# MyRIO_Breakout_Gamma2d.net
KiCad netlist of a schematic drawn in EAGLE
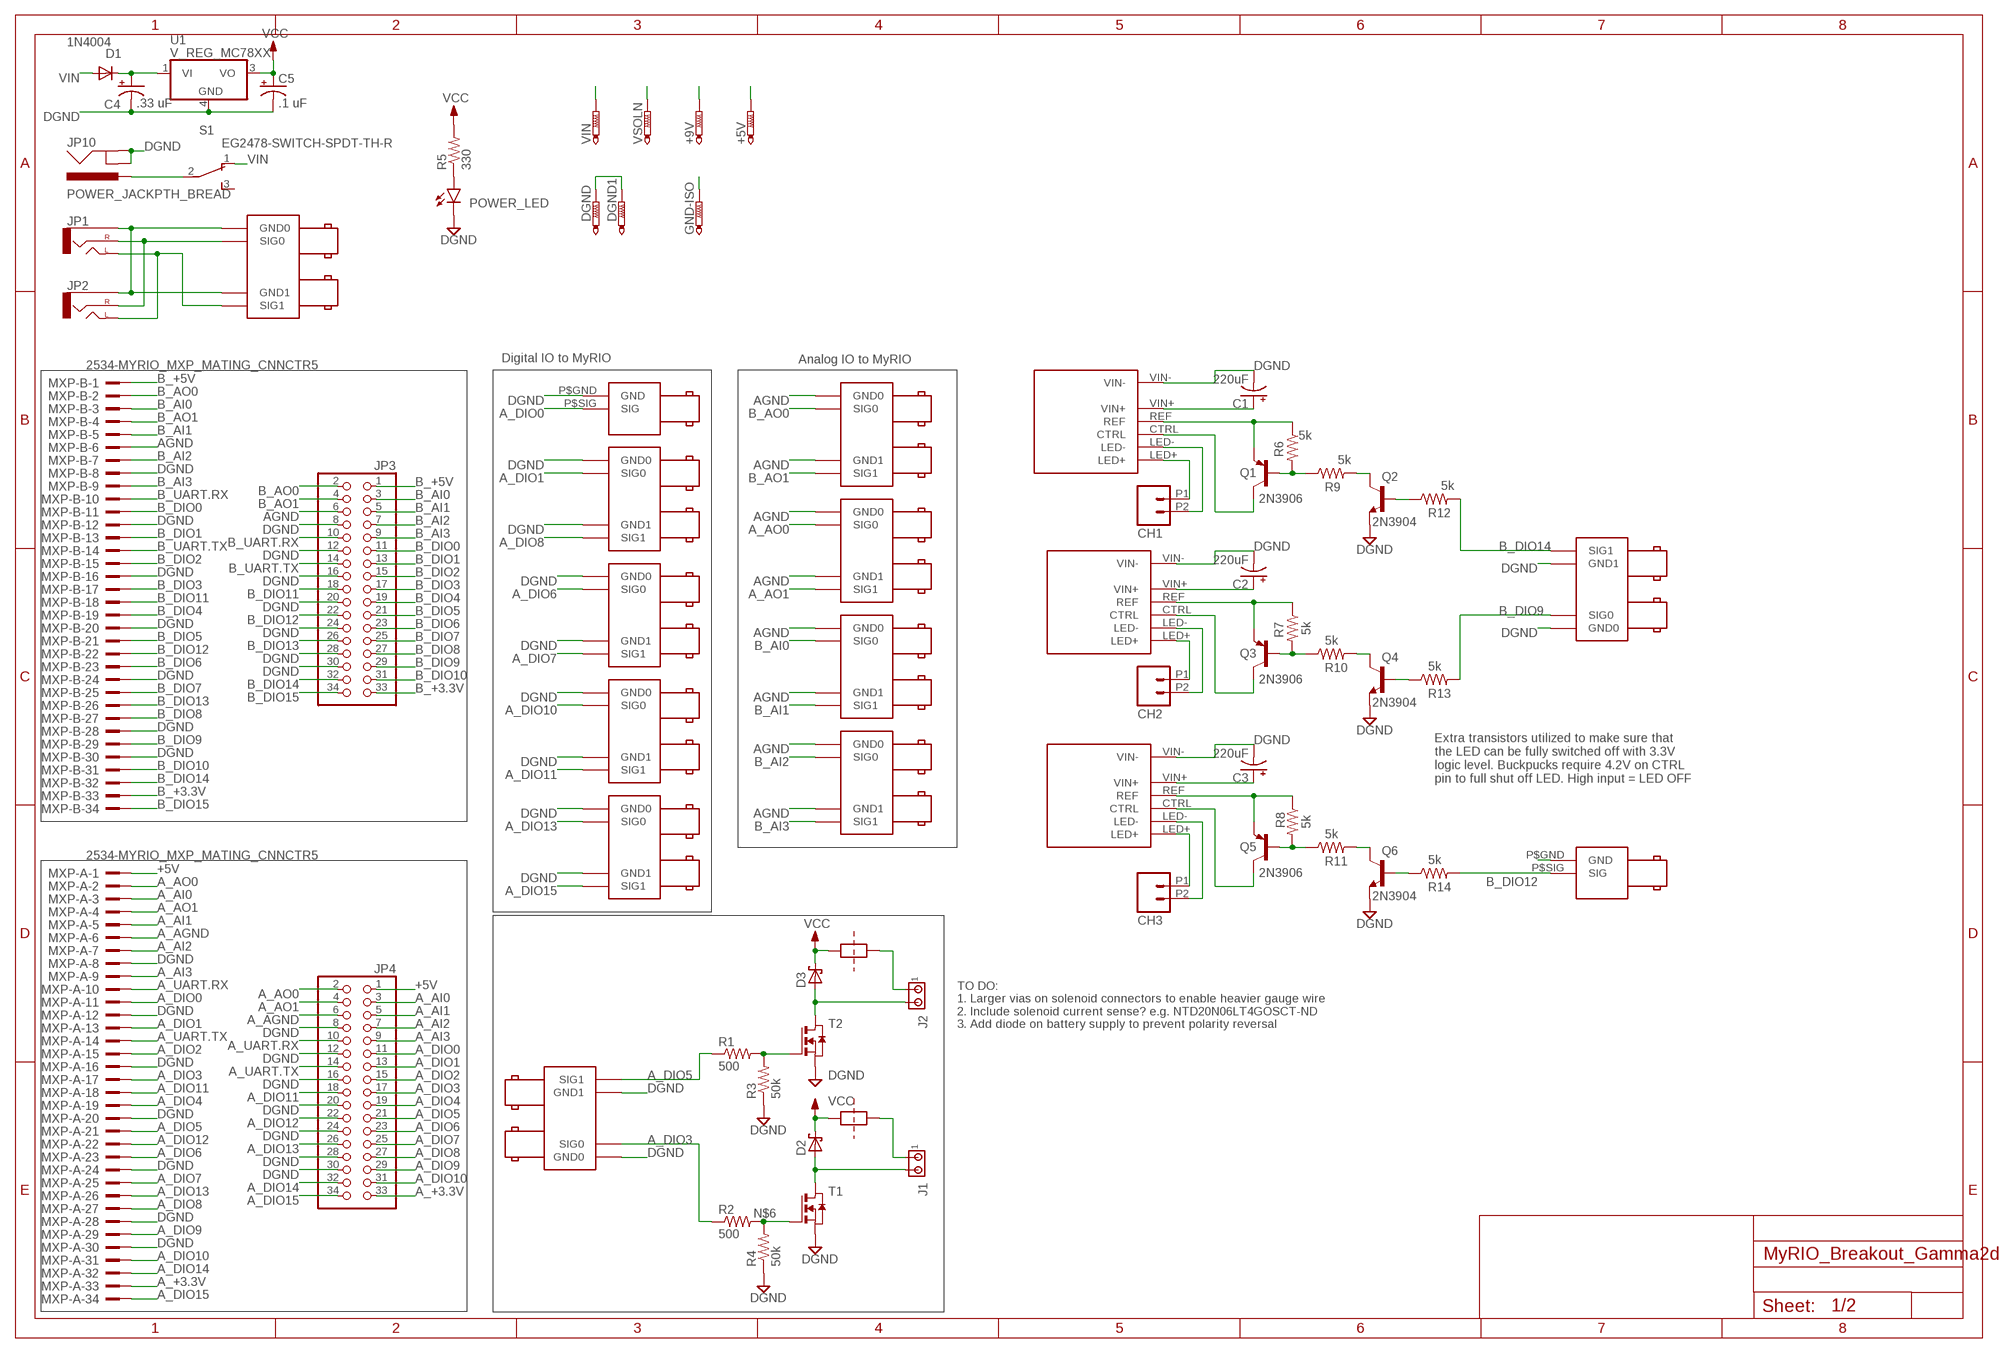
[diagram p0: schematic, sheet 1]
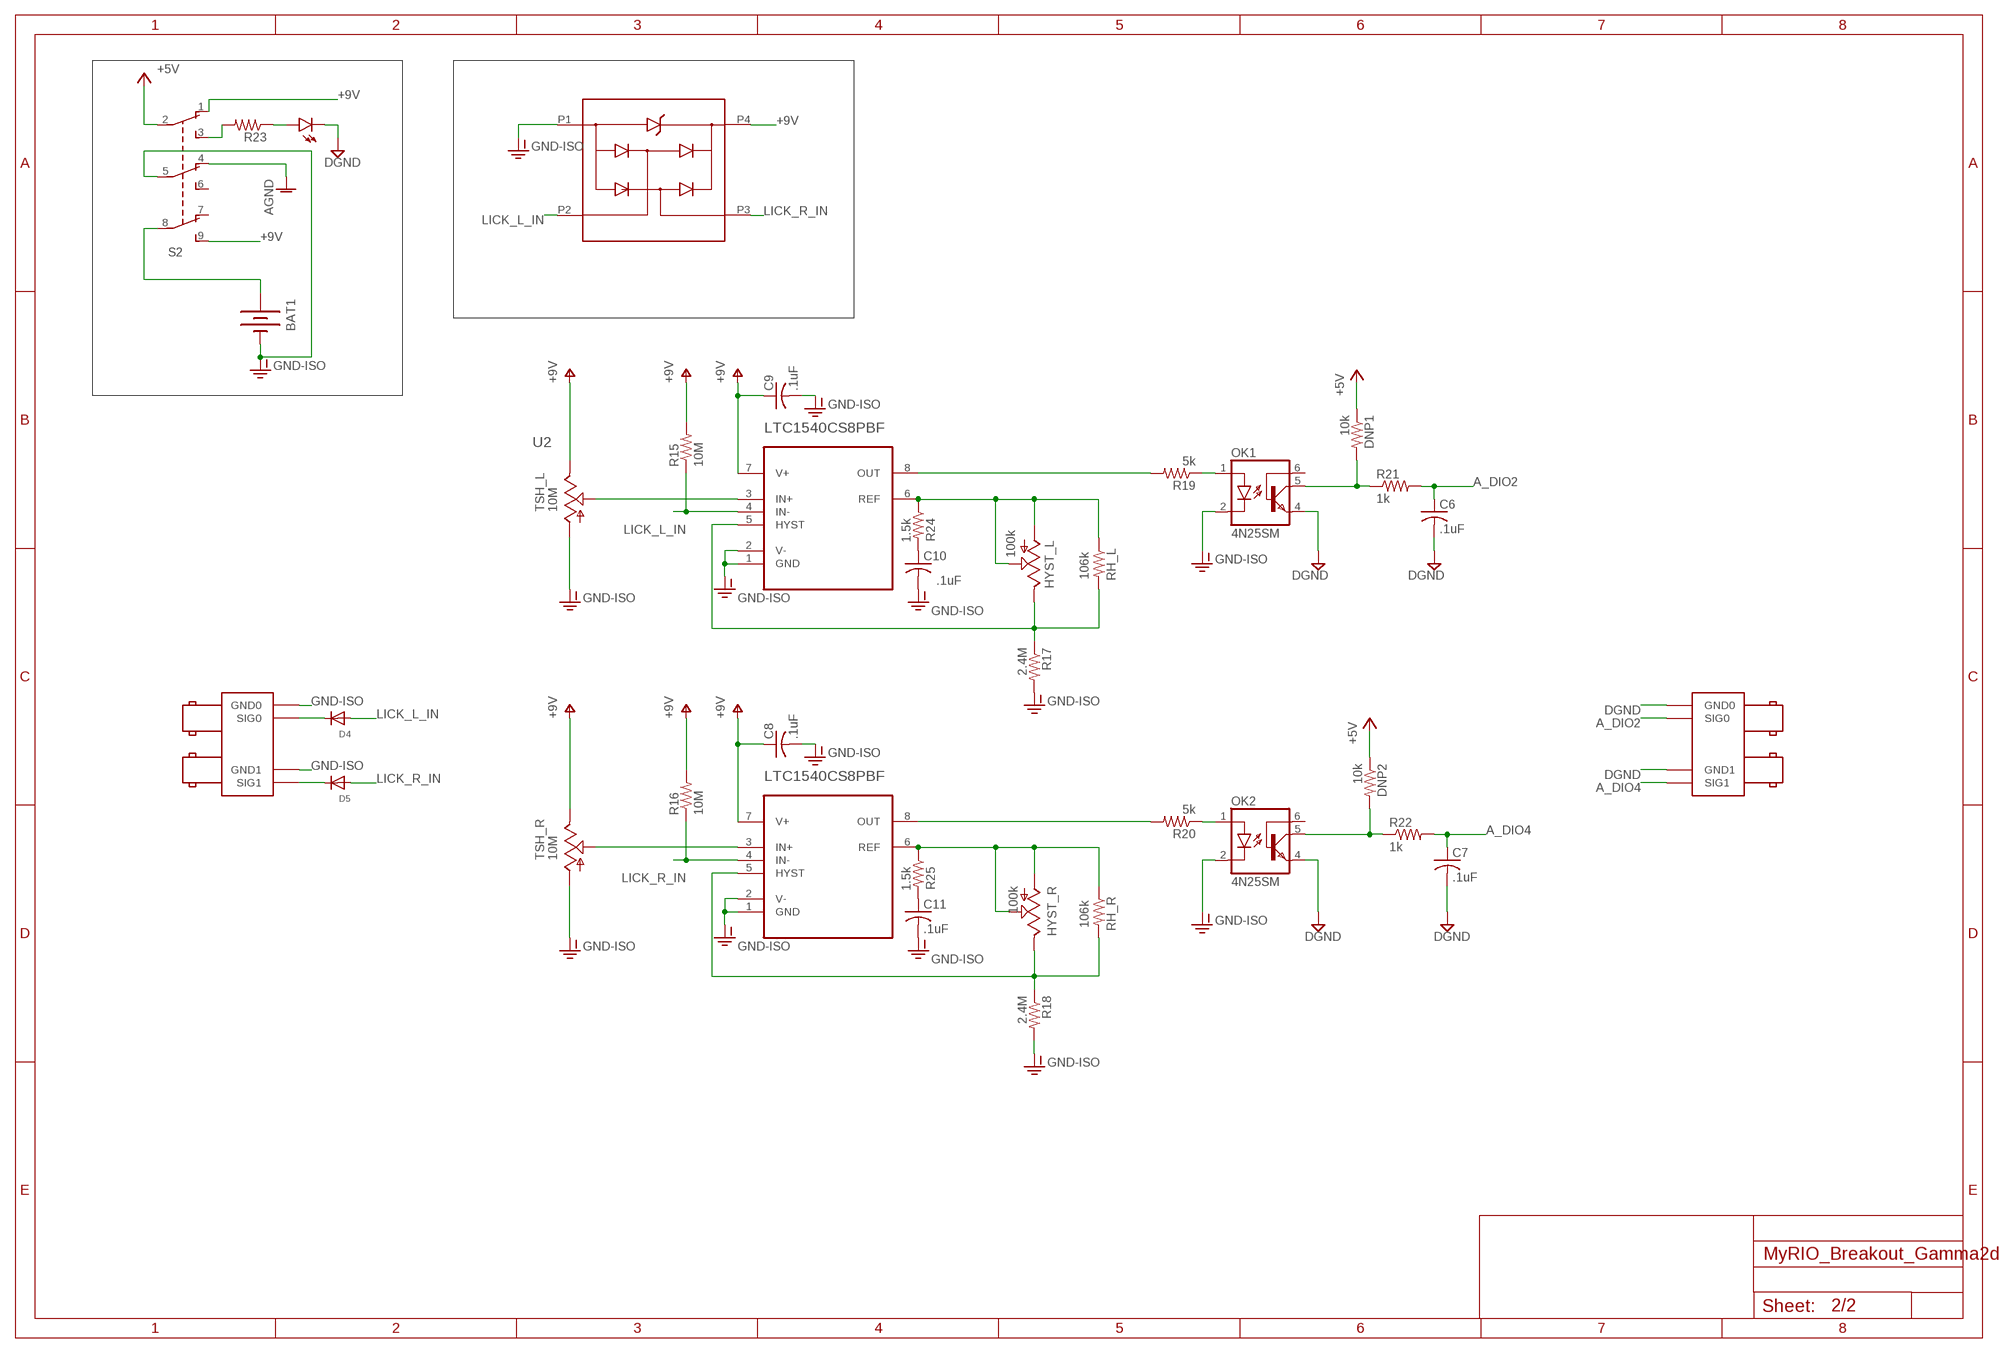
[diagram p1: schematic, sheet 2]

(export (version "E")
  (design (tool "Eeschema 10.0.6"))
  (components
    (comp (ref "+5V")
      (value "PTR1PAD1-13Y")
      (footprint "eagle-import:P1-13Y")
      (libsource (lib "eagle-import") (part "PTR1PAD1-13Y"))
    )
    (comp (ref "+9V")
      (value "PTR1PAD1-13Y")
      (footprint "eagle-import:P1-13Y")
      (libsource (lib "eagle-import") (part "PTR1PAD1-13Y"))
    )
    (comp (ref "AAO_0,1")
      (value "BNC_RIGHT_ANGLE_DOUBLE")
      (footprint "eagle-import:BNC_RIGHT_ANGLE_DOUBLE")
      (libsource (lib "eagle-import") (part "BNC_RIGHT_ANGLE_DOUBLE"))
    )
    (comp (ref "ACTV_REC")
      (value "BNC_RIGHT_ANGLE")
      (footprint "eagle-import:BNC_RIGHT_ANGLE")
      (libsource (lib "eagle-import") (part "BNC_RIGHT_ANGLE"))
    )
    (comp (ref "AUDIO")
      (value "BNC_RIGHT_ANGLE_DOUBLE")
      (footprint "eagle-import:BNC_RIGHT_ANGLE_DOUBLE")
      (libsource (lib "eagle-import") (part "BNC_RIGHT_ANGLE_DOUBLE"))
    )
    (comp (ref "BAI_0,1")
      (value "BNC_RIGHT_ANGLE_DOUBLE")
      (footprint "eagle-import:BNC_RIGHT_ANGLE_DOUBLE")
      (libsource (lib "eagle-import") (part "BNC_RIGHT_ANGLE_DOUBLE"))
    )
    (comp (ref "BAI_2,3")
      (value "BNC_RIGHT_ANGLE_DOUBLE")
      (footprint "eagle-import:BNC_RIGHT_ANGLE_DOUBLE")
      (libsource (lib "eagle-import") (part "BNC_RIGHT_ANGLE_DOUBLE"))
    )
    (comp (ref "BAO_0,1")
      (value "BNC_RIGHT_ANGLE_DOUBLE")
      (footprint "eagle-import:BNC_RIGHT_ANGLE_DOUBLE")
      (libsource (lib "eagle-import") (part "BNC_RIGHT_ANGLE_DOUBLE"))
    )
    (comp (ref "BUCKPUCK1")
      (value "BUCKPUCK-350-I")
      (footprint "eagle-import:BUCKPUCK_I")
      (libsource (lib "eagle-import") (part "BUCKPUCK--?I350"))
    )
    (comp (ref "BUCKPUCK2")
      (value "BUCKPUCK-350-I")
      (footprint "eagle-import:BUCKPUCK_I")
      (libsource (lib "eagle-import") (part "BUCKPUCK--?I350"))
    )
    (comp (ref "BUCKPUCK3")
      (value "BUCKPUCK-350-I")
      (footprint "eagle-import:BUCKPUCK_I")
      (libsource (lib "eagle-import") (part "BUCKPUCK--?I350"))
    )
    (comp (ref "C1")
      (value "220uF")
      (footprint "eagle-import:E5-10,5")
      (libsource (lib "eagle-import") (part "CPOL-USE5-10.5"))
    )
    (comp (ref "C2")
      (value "220uF")
      (footprint "eagle-import:E5-10,5")
      (libsource (lib "eagle-import") (part "CPOL-USE5-10.5"))
    )
    (comp (ref "C3")
      (value "220uF")
      (footprint "eagle-import:E5-10,5")
      (libsource (lib "eagle-import") (part "CPOL-USE5-10.5"))
    )
    (comp (ref "C4")
      (value ".33 uF")
      (footprint "eagle-import:E2,5-5")
      (libsource (lib "eagle-import") (part "CPOL-USE2.5-5"))
    )
    (comp (ref "C5")
      (value ".1 uF")
      (footprint "eagle-import:E2,5-5")
      (libsource (lib "eagle-import") (part "CPOL-USE2.5-5"))
    )
    (comp (ref "CAMERA")
      (value "BNC_RIGHT_ANGLE_DOUBLE")
      (footprint "eagle-import:BNC_RIGHT_ANGLE_DOUBLE")
      (libsource (lib "eagle-import") (part "BNC_RIGHT_ANGLE_DOUBLE"))
    )
    (comp (ref "CH1")
      (value "M022.54MM_SCREWTERM")
      (footprint "eagle-import:1X02_2.54_SCREWTERM")
      (libsource (lib "eagle-import") (part "M022.54MM_SCREWTERM"))
    )
    (comp (ref "CH2")
      (value "M022.54MM_SCREWTERM")
      (footprint "eagle-import:1X02_2.54_SCREWTERM")
      (libsource (lib "eagle-import") (part "M022.54MM_SCREWTERM"))
    )
    (comp (ref "CH3")
      (value "M022.54MM_SCREWTERM")
      (footprint "eagle-import:1X02_2.54_SCREWTERM")
      (libsource (lib "eagle-import") (part "M022.54MM_SCREWTERM"))
    )
    (comp (ref "D1")
      (value "1N4004")
      (footprint "eagle-import:DO41-10")
      (libsource (lib "eagle-import") (part "1N4004"))
    )
    (comp (ref "D2")
      (value "SCHOTTKY-DIODE")
      (footprint "eagle-import:DIODE_SMB")
      (libsource (lib "eagle-import") (part "SCHOTTKY-DIODE"))
    )
    (comp (ref "D3")
      (value "SCHOTTKY-DIODE")
      (footprint "eagle-import:DIODE_SMB")
      (libsource (lib "eagle-import") (part "SCHOTTKY-DIODE"))
    )
    (comp (ref "DGND")
      (value "PTR1PAD1-13Y")
      (footprint "eagle-import:P1-13Y")
      (libsource (lib "eagle-import") (part "PTR1PAD1-13Y"))
    )
    (comp (ref "DGND1")
      (value "PTR1PAD1-13Y")
      (footprint "eagle-import:P1-13Y")
      (libsource (lib "eagle-import") (part "PTR1PAD1-13Y"))
    )
    (comp (ref "D_FREE1_2")
      (value "BNC_RIGHT_ANGLE_DOUBLE")
      (footprint "eagle-import:BNC_RIGHT_ANGLE_DOUBLE")
      (libsource (lib "eagle-import") (part "BNC_RIGHT_ANGLE_DOUBLE"))
    )
    (comp (ref "D_FREE3_4")
      (value "BNC_RIGHT_ANGLE_DOUBLE")
      (footprint "eagle-import:BNC_RIGHT_ANGLE_DOUBLE")
      (libsource (lib "eagle-import") (part "BNC_RIGHT_ANGLE_DOUBLE"))
    )
    (comp (ref "GND-ISO")
      (value "PTR1PAD1-13Y")
      (footprint "eagle-import:P1-13Y")
      (libsource (lib "eagle-import") (part "PTR1PAD1-13Y"))
    )
    (comp (ref "J1")
      (value "MTA02-100")
      (footprint "eagle-import:10X02MTA")
      (libsource (lib "eagle-import") (part "MTA02-100"))
    )
    (comp (ref "J2")
      (value "MTA02-100")
      (footprint "eagle-import:10X02MTA")
      (libsource (lib "eagle-import") (part "MTA02-100"))
    )
    (comp (ref "JP1")
      (value "AUDIO-JACKPTH")
      (footprint "eagle-import:AUDIO-JACK")
      (libsource (lib "eagle-import") (part "AUDIO-JACKPTH"))
    )
    (comp (ref "JP2")
      (value "AUDIO-JACKPTH")
      (footprint "eagle-import:AUDIO-JACK")
      (libsource (lib "eagle-import") (part "AUDIO-JACKPTH"))
    )
    (comp (ref "JP3")
      (value "PINHD-2X17")
      (footprint "eagle-import:2X17")
      (libsource (lib "eagle-import") (part "PINHD-2X17"))
    )
    (comp (ref "JP4")
      (value "PINHD-2X17")
      (footprint "eagle-import:2X17")
      (libsource (lib "eagle-import") (part "PINHD-2X17"))
    )
    (comp (ref "JP5")
      (value "CUTABLE_RESISTOR_JUMPER1206")
      (footprint "eagle-import:1206_WITH_TRACE")
      (libsource (lib "eagle-import") (part "CUTABLE_RESISTOR_JUMPER1206"))
    )
    (comp (ref "JP6")
      (value "CUTABLE_RESISTOR_JUMPER1206")
      (footprint "eagle-import:1206_WITH_TRACE")
      (libsource (lib "eagle-import") (part "CUTABLE_RESISTOR_JUMPER1206"))
    )
    (comp (ref "JP10")
      (value "POWER_JACKPTH_BREAD")
      (footprint "eagle-import:POWER_JACK_PTH_BREAD")
      (libsource (lib "eagle-import") (part "POWER_JACKPTH_BREAD"))
    )
    (comp (ref "LED_CUE_3")
      (value "BNC_RIGHT_ANGLE")
      (footprint "eagle-import:BNC_RIGHT_ANGLE")
      (libsource (lib "eagle-import") (part "BNC_RIGHT_ANGLE"))
    )
    (comp (ref "LED_MASK_1,2")
      (value "BNC_RIGHT_ANGLE_DOUBLE")
      (footprint "eagle-import:BNC_RIGHT_ANGLE_DOUBLE")
      (libsource (lib "eagle-import") (part "BNC_RIGHT_ANGLE_DOUBLE"))
    )
    (comp (ref "MXP-A")
      (value "2534-MYRIO_MXP_MATING_CNNCTR5")
      (footprint "eagle-import:PAK100_2500-5-34-MXP_CONNCTR")
      (libsource (lib "eagle-import") (part "2534-MYRIO_MXP_MATING_CNNCTR5"))
    )
    (comp (ref "MXP-B")
      (value "2534-MYRIO_MXP_MATING_CNNCTR5")
      (footprint "eagle-import:PAK100_2500-5-34-MXP_CONNCTR")
      (libsource (lib "eagle-import") (part "2534-MYRIO_MXP_MATING_CNNCTR5"))
    )
    (comp (ref "POWER_LED")
      (value "LED3MM")
      (footprint "eagle-import:LED3MM")
      (libsource (lib "eagle-import") (part "LED3MM"))
    )
    (comp (ref "Q1")
      (value "2N3906")
      (footprint "eagle-import:SOT23-BEC")
      (libsource (lib "eagle-import") (part "-PNP-SOT23-BECMMBT3906LT1"))
    )
    (comp (ref "Q2")
      (value "2N3904")
      (footprint "eagle-import:SOT23-BEC")
      (libsource (lib "eagle-import") (part "-NPN-SOT23-BECMMBT3904LT1"))
    )
    (comp (ref "Q3")
      (value "2N3906")
      (footprint "eagle-import:SOT23-BEC")
      (libsource (lib "eagle-import") (part "-PNP-SOT23-BECMMBT3906LT1"))
    )
    (comp (ref "Q4")
      (value "2N3904")
      (footprint "eagle-import:SOT23-BEC")
      (libsource (lib "eagle-import") (part "-NPN-SOT23-BECMMBT3904LT1"))
    )
    (comp (ref "Q5")
      (value "2N3906")
      (footprint "eagle-import:SOT23-BEC")
      (libsource (lib "eagle-import") (part "-PNP-SOT23-BECMMBT3906LT1"))
    )
    (comp (ref "Q6")
      (value "2N3904")
      (footprint "eagle-import:SOT23-BEC")
      (libsource (lib "eagle-import") (part "-NPN-SOT23-BECMMBT3904LT1"))
    )
    (comp (ref "R1")
      (value "500")
      (footprint "eagle-import:M1206")
      (libsource (lib "eagle-import") (part "R-US_M1206"))
    )
    (comp (ref "R2")
      (value "500")
      (footprint "eagle-import:M1206")
      (libsource (lib "eagle-import") (part "R-US_M1206"))
    )
    (comp (ref "R3")
      (value "50k")
      (footprint "eagle-import:M1206")
      (libsource (lib "eagle-import") (part "R-US_M1206"))
    )
    (comp (ref "R4")
      (value "50k")
      (footprint "eagle-import:M1206")
      (libsource (lib "eagle-import") (part "R-US_M1206"))
    )
    (comp (ref "R5")
      (value "330")
      (footprint "eagle-import:0207_10")
      (libsource (lib "eagle-import") (part "R-US_0207/10"))
    )
    (comp (ref "R6")
      (value "5k")
      (footprint "eagle-import:0805S")
      (libsource (lib "eagle-import") (part "RESISTOR_SM0805S"))
    )
    (comp (ref "R7")
      (value "5k")
      (footprint "eagle-import:0805S")
      (libsource (lib "eagle-import") (part "RESISTOR_SM0805S"))
    )
    (comp (ref "R8")
      (value "5k")
      (footprint "eagle-import:0805S")
      (libsource (lib "eagle-import") (part "RESISTOR_SM0805S"))
    )
    (comp (ref "R9")
      (value "5k")
      (footprint "eagle-import:0805S")
      (libsource (lib "eagle-import") (part "RESISTOR_SM0805S"))
    )
    (comp (ref "R10")
      (value "5k")
      (footprint "eagle-import:0805S")
      (libsource (lib "eagle-import") (part "RESISTOR_SM0805S"))
    )
    (comp (ref "R11")
      (value "5k")
      (footprint "eagle-import:0805S")
      (libsource (lib "eagle-import") (part "RESISTOR_SM0805S"))
    )
    (comp (ref "R12")
      (value "5k")
      (footprint "eagle-import:0805S")
      (libsource (lib "eagle-import") (part "RESISTOR_SM0805S"))
    )
    (comp (ref "R13")
      (value "5k")
      (footprint "eagle-import:0805S")
      (libsource (lib "eagle-import") (part "RESISTOR_SM0805S"))
    )
    (comp (ref "R14")
      (value "5k")
      (footprint "eagle-import:0805S")
      (libsource (lib "eagle-import") (part "RESISTOR_SM0805S"))
    )
    (comp (ref "S1")
      (value "EG2478-SWITCH-SPDT-TH-R")
      (footprint "eagle-import:ESWITCH_500-SSP1M6")
      (libsource (lib "eagle-import") (part "EG2478-SWITCH-SPDT-TH-R"))
    )
    (comp (ref "SHUTTER")
      (value "BNC_RIGHT_ANGLE_DOUBLE")
      (footprint "eagle-import:BNC_RIGHT_ANGLE_DOUBLE")
      (libsource (lib "eagle-import") (part "BNC_RIGHT_ANGLE_DOUBLE"))
    )
    (comp (ref "SLN")
      (value "BNC_RIGHT_ANGLE_DOUBLE")
      (footprint "eagle-import:BNC_RIGHT_ANGLE_DOUBLE")
      (libsource (lib "eagle-import") (part "BNC_RIGHT_ANGLE_DOUBLE"))
    )
    (comp (ref "T1")
      (value "NMOSSOT223")
      (footprint "eagle-import:SOT223")
      (libsource (lib "eagle-import") (part "NMOSSOT223"))
    )
    (comp (ref "T2")
      (value "NMOSSOT223")
      (footprint "eagle-import:SOT223")
      (libsource (lib "eagle-import") (part "NMOSSOT223"))
    )
    (comp (ref "U1")
      (value "V_REG_MC78XX")
      (footprint "eagle-import:DPAK")
      (libsource (lib "eagle-import") (part "V_REG_MC78XX"))
    )
    (comp (ref "VIN")
      (value "PTR1PAD1-13Y")
      (footprint "eagle-import:P1-13Y")
      (libsource (lib "eagle-import") (part "PTR1PAD1-13Y"))
    )
    (comp (ref "VSOLN")
      (value "PTR1PAD1-13Y")
      (footprint "eagle-import:P1-13Y")
      (libsource (lib "eagle-import") (part "PTR1PAD1-13Y"))
    )
    (comp (ref "BAT1")
      (value "BATTERY9V")
      (footprint "eagle-import:BATTCON_9V")
      (libsource (lib "eagle-import") (part "BATTERY9V"))
    )
    (comp (ref "C6")
      (value ".1uF")
      (footprint "eagle-import:C0805")
      (libsource (lib "eagle-import") (part "C-USC0805"))
    )
    (comp (ref "C7")
      (value ".1uF")
      (footprint "eagle-import:C0805")
      (fields (field (name "SPICEPREFIX") "C"))
      (libsource (lib "eagle-import") (part "C-USC0805"))
    )
    (comp (ref "C8")
      (value ".1uF")
      (footprint "eagle-import:C0805")
      (fields (field (name "SPICEPREFIX") "C"))
      (libsource (lib "eagle-import") (part "C-USC0805"))
    )
    (comp (ref "C9")
      (value ".1uF")
      (footprint "eagle-import:C0805")
      (fields (field (name "SPICEPREFIX") "C"))
      (libsource (lib "eagle-import") (part "C-USC0805"))
    )
    (comp (ref "C10")
      (value ".1uF")
      (footprint "eagle-import:C0805")
      (fields (field (name "SPICEPREFIX") "C"))
      (libsource (lib "eagle-import") (part "C-USC0805"))
    )
    (comp (ref "C11")
      (value ".1uF")
      (footprint "eagle-import:C0805")
      (fields (field (name "SPICEPREFIX") "C"))
      (libsource (lib "eagle-import") (part "C-USC0805"))
    )
    (comp (ref "D4")
      (value "DIODE_SOD-123FL")
      (footprint "eagle-import:SOD-123FL")
      (libsource (lib "eagle-import") (part "DIODE_SOD-123FL"))
    )
    (comp (ref "D5")
      (value "DIODE_SOD-123FL")
      (footprint "eagle-import:SOD-123FL")
      (libsource (lib "eagle-import") (part "DIODE_SOD-123FL"))
    )
    (comp (ref "DNP1")
      (value "10k")
      (footprint "eagle-import:M0805")
      (libsource (lib "eagle-import") (part "R-US_M0805"))
    )
    (comp (ref "DNP2")
      (value "10k")
      (footprint "eagle-import:M0805")
      (fields (field (name "SPICEPREFIX") "R"))
      (libsource (lib "eagle-import") (part "R-US_M0805"))
    )
    (comp (ref "HYST_L")
      (value "100k")
      (footprint "eagle-import:B25P")
      (libsource (lib "eagle-import") (part "TRIM_US-B25P"))
    )
    (comp (ref "HYST_R")
      (value "100k")
      (footprint "eagle-import:B25P")
      (fields (field (name "SPICEPREFIX") "J"))
      (libsource (lib "eagle-import") (part "TRIM_US-B25P"))
    )
    (comp (ref "ISOLATED")
      (value "LED3MM")
      (footprint "eagle-import:LED3MM")
      (libsource (lib "eagle-import") (part "LED3MM"))
    )
    (comp (ref "LICK")
      (value "BNC_RIGHT_ANGLE_DOUBLE")
      (footprint "eagle-import:BNC_RIGHT_ANGLE_DOUBLE")
      (libsource (lib "eagle-import") (part "BNC_RIGHT_ANGLE_DOUBLE"))
    )
    (comp (ref "LICK_INPUTS")
      (value "BNC_RIGHT_ANGLE_DOUBLE")
      (footprint "eagle-import:BNC_RIGHT_ANGLE_DOUBLE")
      (libsource (lib "eagle-import") (part "BNC_RIGHT_ANGLE_DOUBLE"))
    )
    (comp (ref "OK1")
      (value "4N25SM")
      (footprint "eagle-import:DIL6-SMD")
      (fields (field (name "MF") "FAIRCHILD SEMICONDUCTOR"))
      (libsource (lib "eagle-import") (part "4N?MS25"))
    )
    (comp (ref "OK2")
      (value "4N25SM")
      (footprint "eagle-import:DIL6-SMD")
      (fields (field (name "MF") "FAIRCHILD SEMICONDUCTOR") (field (name "SPICEPREFIX") "X"))
      (libsource (lib "eagle-import") (part "4N?MS25"))
    )
    (comp (ref "R15")
      (value "10M")
      (footprint "eagle-import:M0805")
      (fields (field (name "SPICEPREFIX") "R"))
      (libsource (lib "eagle-import") (part "R-US_M0805"))
    )
    (comp (ref "R16")
      (value "10M")
      (footprint "eagle-import:M0805")
      (fields (field (name "SPICEPREFIX") "R"))
      (libsource (lib "eagle-import") (part "R-US_M0805"))
    )
    (comp (ref "R17")
      (value "2.4M")
      (footprint "eagle-import:M0805")
      (libsource (lib "eagle-import") (part "R-US_M0805"))
    )
    (comp (ref "R18")
      (value "2.4M")
      (footprint "eagle-import:M0805")
      (fields (field (name "SPICEPREFIX") "R"))
      (libsource (lib "eagle-import") (part "R-US_M0805"))
    )
    (comp (ref "R19")
      (value "5k")
      (footprint "eagle-import:M0805")
      (libsource (lib "eagle-import") (part "R-US_M0805"))
    )
    (comp (ref "R20")
      (value "5k")
      (footprint "eagle-import:M0805")
      (fields (field (name "SPICEPREFIX") "R"))
      (libsource (lib "eagle-import") (part "R-US_M0805"))
    )
    (comp (ref "R21")
      (value "1k")
      (footprint "eagle-import:M0805")
      (libsource (lib "eagle-import") (part "R-US_M0805"))
    )
    (comp (ref "R22")
      (value "1k")
      (footprint "eagle-import:M0805")
      (fields (field (name "SPICEPREFIX") "R"))
      (libsource (lib "eagle-import") (part "R-US_M0805"))
    )
    (comp (ref "R23")
      (value "330")
      (footprint "eagle-import:0207_10")
      (libsource (lib "eagle-import") (part "R-US_0207/10"))
    )
    (comp (ref "R24")
      (value "1.5k")
      (footprint "eagle-import:M0805")
      (libsource (lib "eagle-import") (part "R-US_M0805"))
    )
    (comp (ref "R25")
      (value "1.5k")
      (footprint "eagle-import:M0805")
      (libsource (lib "eagle-import") (part "R-US_M0805"))
    )
    (comp (ref "RH_L")
      (value "106k")
      (footprint "eagle-import:M0805")
      (libsource (lib "eagle-import") (part "R-US_M0805"))
    )
    (comp (ref "RH_R")
      (value "106k")
      (footprint "eagle-import:M0805")
      (libsource (lib "eagle-import") (part "R-US_M0805"))
    )
    (comp (ref "S2")
      (value "SWITCH-3PDT-TH-V")
      (footprint "eagle-import:NKK-M20-9PIN-VERTICAL")
      (libsource (lib "eagle-import") (part "SWITCH-3PDT-TH-V"))
    )
    (comp (ref "TSH_L")
      (value "10M")
      (footprint "eagle-import:B25P")
      (libsource (lib "eagle-import") (part "TRIM_US-B25P"))
    )
    (comp (ref "TSH_R")
      (value "10M")
      (footprint "eagle-import:B25P")
      (libsource (lib "eagle-import") (part "TRIM_US-B25P"))
    )
    (comp (ref "U$1")
      (value "CD143A-12_TVS")
      (footprint "eagle-import:SOT-143")
      (libsource (lib "eagle-import") (part "CD143A-12_TVS"))
    )
    (comp (ref "U2")
      (value "LTC1540CS8PBF")
      (footprint "eagle-import:SOIC127P600X175-8N")
      (fields (field (name "MF") "Linear Technology/Analog") (field (name "MP") "LTC1540CS8#PBF"))
      (libsource (lib "eagle-import") (part "LTC1540CS8PBF"))
    )
    (comp (ref "U3")
      (value "LTC1540CS8PBF")
      (footprint "eagle-import:SOIC127P600X175-8N")
      (fields
        (field (name "MF") "Linear Technology/Analog")
        (field (name "MP") "LTC1540CS8#PBF")
        (field (name "SPICEPREFIX") "X")
      )
      (libsource (lib "eagle-import") (part "LTC1540CS8PBF"))
    )
  )
  (nets
    (net (code "1") (name "+5V") (class "Default")
      (node (ref "+5V") (pin "TP") (pinfunction "TP_TP") (pintype "input"))
      (node (ref "DNP1") (pin "1") (pinfunction "1_1") (pintype "passive"))
      (node (ref "DNP2") (pin "1") (pinfunction "1_1") (pintype "passive"))
      (node (ref "JP4") (pin "1") (pinfunction "1_1") (pintype "passive"))
      (node (ref "MXP-A") (pin "1") (pinfunction "KL_1") (pintype "passive"))
      (node (ref "S2") (pin "2") (pinfunction "P1_2") (pintype "passive"))
    )
    (net (code "2") (name "+9V") (class "Default")
      (node (ref "+9V") (pin "TP") (pinfunction "TP_TP") (pintype "input"))
      (node (ref "C8") (pin "1") (pinfunction "1_1") (pintype "passive"))
      (node (ref "C9") (pin "1") (pinfunction "1_1") (pintype "passive"))
      (node (ref "R15") (pin "2") (pinfunction "2_2") (pintype "passive"))
      (node (ref "R16") (pin "2") (pinfunction "2_2") (pintype "passive"))
      (node (ref "S2") (pin "1") (pinfunction "O1_1") (pintype "passive"))
      (node (ref "S2") (pin "9") (pinfunction "S3_9") (pintype "passive"))
      (node (ref "TSH_L") (pin "E") (pinfunction "E_E") (pintype "passive"))
      (node (ref "TSH_R") (pin "E") (pinfunction "E_E") (pintype "passive"))
      (node (ref "U$1") (pin "P4") (pinfunction "P$4_P4") (pintype "bidirectional"))
      (node (ref "U2") (pin "7") (pinfunction "V+_7") (pintype "power_in"))
      (node (ref "U3") (pin "7") (pinfunction "V+_7") (pintype "power_in"))
    )
    (net (code "3") (name "AGND") (class "Default")
      (node (ref "AAO_0,1") (pin "P$GND0") (pinfunction "GND0_P$GND0") (pintype "bidirectional"))
      (node (ref "AAO_0,1") (pin "P$GND1") (pinfunction "GND1_P$GND1") (pintype "bidirectional"))
      (node (ref "BAI_0,1") (pin "P$GND0") (pinfunction "GND0_P$GND0") (pintype "bidirectional"))
      (node (ref "BAI_0,1") (pin "P$GND1") (pinfunction "GND1_P$GND1") (pintype "bidirectional"))
      (node (ref "BAI_2,3") (pin "P$GND0") (pinfunction "GND0_P$GND0") (pintype "bidirectional"))
      (node (ref "BAI_2,3") (pin "P$GND1") (pinfunction "GND1_P$GND1") (pintype "bidirectional"))
      (node (ref "BAO_0,1") (pin "P$GND0") (pinfunction "GND0_P$GND0") (pintype "bidirectional"))
      (node (ref "BAO_0,1") (pin "P$GND1") (pinfunction "GND1_P$GND1") (pintype "bidirectional"))
      (node (ref "JP3") (pin "6") (pinfunction "6_6") (pintype "passive"))
      (node (ref "MXP-B") (pin "6") (pinfunction "KL_6") (pintype "passive"))
      (node (ref "S2") (pin "4") (pinfunction "O2_4") (pintype "passive"))
    )
    (net (code "4") (name "A_+3.3V") (class "Default")
      (node (ref "JP4") (pin "33") (pinfunction "33_33") (pintype "passive"))
      (node (ref "MXP-A") (pin "33") (pinfunction "KL_33") (pintype "passive"))
    )
    (net (code "5") (name "A_AGND") (class "Default")
      (node (ref "JP4") (pin "6") (pinfunction "6_6") (pintype "passive"))
      (node (ref "MXP-A") (pin "6") (pinfunction "KL_6") (pintype "passive"))
    )
    (net (code "6") (name "A_AI0") (class "Default")
      (node (ref "JP4") (pin "3") (pinfunction "3_3") (pintype "passive"))
      (node (ref "MXP-A") (pin "3") (pinfunction "KL_3") (pintype "passive"))
    )
    (net (code "7") (name "A_AI1") (class "Default")
      (node (ref "JP4") (pin "5") (pinfunction "5_5") (pintype "passive"))
      (node (ref "MXP-A") (pin "5") (pinfunction "KL_5") (pintype "passive"))
    )
    (net (code "8") (name "A_AI2") (class "Default")
      (node (ref "JP4") (pin "7") (pinfunction "7_7") (pintype "passive"))
      (node (ref "MXP-A") (pin "7") (pinfunction "KL_7") (pintype "passive"))
    )
    (net (code "9") (name "A_AI3") (class "Default")
      (node (ref "JP4") (pin "9") (pinfunction "9_9") (pintype "passive"))
      (node (ref "MXP-A") (pin "9") (pinfunction "KL_9") (pintype "passive"))
    )
    (net (code "10") (name "A_AO0") (class "Default")
      (node (ref "AAO_0,1") (pin "P$SIG0") (pinfunction "SIG0_P$SIG0") (pintype "bidirectional"))
      (node (ref "JP4") (pin "2") (pinfunction "2_2") (pintype "passive"))
      (node (ref "MXP-A") (pin "2") (pinfunction "KL_2") (pintype "passive"))
    )
    (net (code "11") (name "A_AO1") (class "Default")
      (node (ref "AAO_0,1") (pin "P$SIG1") (pinfunction "SIG1_P$SIG1") (pintype "bidirectional"))
      (node (ref "JP4") (pin "4") (pinfunction "4_4") (pintype "passive"))
      (node (ref "MXP-A") (pin "4") (pinfunction "KL_4") (pintype "passive"))
    )
    (net (code "12") (name "A_DIO0") (class "Default")
      (node (ref "ACTV_REC") (pin "P$SIG") (pinfunction "SIG_P$SIG") (pintype "bidirectional"))
      (node (ref "JP4") (pin "11") (pinfunction "11_11") (pintype "passive"))
      (node (ref "MXP-A") (pin "11") (pinfunction "KL_11") (pintype "passive"))
    )
    (net (code "13") (name "A_DIO1") (class "Default")
      (node (ref "CAMERA") (pin "P$SIG0") (pinfunction "SIG0_P$SIG0") (pintype "bidirectional"))
      (node (ref "JP4") (pin "13") (pinfunction "13_13") (pintype "passive"))
      (node (ref "MXP-A") (pin "13") (pinfunction "KL_13") (pintype "passive"))
    )
    (net (code "14") (name "A_DIO2") (class "Default")
      (node (ref "C6") (pin "1") (pinfunction "1_1") (pintype "passive"))
      (node (ref "JP4") (pin "15") (pinfunction "15_15") (pintype "passive"))
      (node (ref "LICK") (pin "P$SIG0") (pinfunction "SIG0_P$SIG0") (pintype "bidirectional"))
      (node (ref "MXP-A") (pin "15") (pinfunction "KL_15") (pintype "passive"))
      (node (ref "R21") (pin "2") (pinfunction "2_2") (pintype "passive"))
    )
    (net (code "15") (name "A_DIO3") (class "Default")
      (node (ref "JP4") (pin "17") (pinfunction "17_17") (pintype "passive"))
      (node (ref "MXP-A") (pin "17") (pinfunction "KL_17") (pintype "passive"))
      (node (ref "R2") (pin "1") (pinfunction "1_1") (pintype "passive"))
      (node (ref "SLN") (pin "P$SIG0") (pinfunction "SIG0_P$SIG0") (pintype "bidirectional"))
    )
    (net (code "16") (name "A_DIO4") (class "Default")
      (node (ref "C7") (pin "1") (pinfunction "1_1") (pintype "passive"))
      (node (ref "JP4") (pin "19") (pinfunction "19_19") (pintype "passive"))
      (node (ref "LICK") (pin "P$SIG1") (pinfunction "SIG1_P$SIG1") (pintype "bidirectional"))
      (node (ref "MXP-A") (pin "19") (pinfunction "KL_19") (pintype "passive"))
      (node (ref "R22") (pin "2") (pinfunction "2_2") (pintype "passive"))
    )
    (net (code "17") (name "A_DIO5") (class "Default")
      (node (ref "JP4") (pin "21") (pinfunction "21_21") (pintype "passive"))
      (node (ref "MXP-A") (pin "21") (pinfunction "KL_21") (pintype "passive"))
      (node (ref "R1") (pin "1") (pinfunction "1_1") (pintype "passive"))
      (node (ref "SLN") (pin "P$SIG1") (pinfunction "SIG1_P$SIG1") (pintype "bidirectional"))
    )
    (net (code "18") (name "A_DIO6") (class "Default")
      (node (ref "JP4") (pin "23") (pinfunction "23_23") (pintype "passive"))
      (node (ref "MXP-A") (pin "23") (pinfunction "KL_23") (pintype "passive"))
      (node (ref "SHUTTER") (pin "P$SIG0") (pinfunction "SIG0_P$SIG0") (pintype "bidirectional"))
    )
    (net (code "19") (name "A_DIO7") (class "Default")
      (node (ref "JP4") (pin "25") (pinfunction "25_25") (pintype "passive"))
      (node (ref "MXP-A") (pin "25") (pinfunction "KL_25") (pintype "passive"))
      (node (ref "SHUTTER") (pin "P$SIG1") (pinfunction "SIG1_P$SIG1") (pintype "bidirectional"))
    )
    (net (code "20") (name "A_DIO8") (class "Default")
      (node (ref "CAMERA") (pin "P$SIG1") (pinfunction "SIG1_P$SIG1") (pintype "bidirectional"))
      (node (ref "JP4") (pin "27") (pinfunction "27_27") (pintype "passive"))
      (node (ref "MXP-A") (pin "27") (pinfunction "KL_27") (pintype "passive"))
    )
    (net (code "21") (name "A_DIO9") (class "Default")
      (node (ref "JP4") (pin "29") (pinfunction "29_29") (pintype "passive"))
      (node (ref "MXP-A") (pin "29") (pinfunction "KL_29") (pintype "passive"))
    )
    (net (code "22") (name "A_DIO10") (class "Default")
      (node (ref "D_FREE1_2") (pin "P$SIG0") (pinfunction "SIG0_P$SIG0") (pintype "bidirectional"))
      (node (ref "JP4") (pin "31") (pinfunction "31_31") (pintype "passive"))
      (node (ref "MXP-A") (pin "31") (pinfunction "KL_31") (pintype "passive"))
    )
    (net (code "23") (name "A_DIO11") (class "Default")
      (node (ref "D_FREE1_2") (pin "P$SIG1") (pinfunction "SIG1_P$SIG1") (pintype "bidirectional"))
      (node (ref "JP4") (pin "18") (pinfunction "18_18") (pintype "passive"))
      (node (ref "MXP-A") (pin "18") (pinfunction "KL_18") (pintype "passive"))
    )
    (net (code "24") (name "A_DIO12") (class "Default")
      (node (ref "JP4") (pin "22") (pinfunction "22_22") (pintype "passive"))
      (node (ref "MXP-A") (pin "22") (pinfunction "KL_22") (pintype "passive"))
    )
    (net (code "25") (name "A_DIO13") (class "Default")
      (node (ref "D_FREE3_4") (pin "P$SIG0") (pinfunction "SIG0_P$SIG0") (pintype "bidirectional"))
      (node (ref "JP4") (pin "26") (pinfunction "26_26") (pintype "passive"))
      (node (ref "MXP-A") (pin "26") (pinfunction "KL_26") (pintype "passive"))
    )
    (net (code "26") (name "A_DIO14") (class "Default")
      (node (ref "JP4") (pin "32") (pinfunction "32_32") (pintype "passive"))
      (node (ref "MXP-A") (pin "32") (pinfunction "KL_32") (pintype "passive"))
    )
    (net (code "27") (name "A_DIO15") (class "Default")
      (node (ref "D_FREE3_4") (pin "P$SIG1") (pinfunction "SIG1_P$SIG1") (pintype "bidirectional"))
      (node (ref "JP4") (pin "34") (pinfunction "34_34") (pintype "passive"))
      (node (ref "MXP-A") (pin "34") (pinfunction "KL_34") (pintype "passive"))
    )
    (net (code "28") (name "A_UART.RX") (class "Default")
      (node (ref "JP4") (pin "10") (pinfunction "10_10") (pintype "passive"))
      (node (ref "MXP-A") (pin "10") (pinfunction "KL_10") (pintype "passive"))
    )
    (net (code "29") (name "A_UART.TX") (class "Default")
      (node (ref "JP4") (pin "14") (pinfunction "14_14") (pintype "passive"))
      (node (ref "MXP-A") (pin "14") (pinfunction "KL_14") (pintype "passive"))
    )
    (net (code "30") (name "B_+3.3V") (class "Default")
      (node (ref "JP3") (pin "33") (pinfunction "33_33") (pintype "passive"))
      (node (ref "MXP-B") (pin "33") (pinfunction "KL_33") (pintype "passive"))
    )
    (net (code "31") (name "B_+5V") (class "Default")
      (node (ref "JP3") (pin "1") (pinfunction "1_1") (pintype "passive"))
      (node (ref "MXP-B") (pin "1") (pinfunction "KL_1") (pintype "passive"))
    )
    (net (code "32") (name "B_AI0") (class "Default")
      (node (ref "BAI_0,1") (pin "P$SIG0") (pinfunction "SIG0_P$SIG0") (pintype "bidirectional"))
      (node (ref "JP3") (pin "3") (pinfunction "3_3") (pintype "passive"))
      (node (ref "MXP-B") (pin "3") (pinfunction "KL_3") (pintype "passive"))
    )
    (net (code "33") (name "B_AI1") (class "Default")
      (node (ref "BAI_0,1") (pin "P$SIG1") (pinfunction "SIG1_P$SIG1") (pintype "bidirectional"))
      (node (ref "JP3") (pin "5") (pinfunction "5_5") (pintype "passive"))
      (node (ref "MXP-B") (pin "5") (pinfunction "KL_5") (pintype "passive"))
    )
    (net (code "34") (name "B_AI2") (class "Default")
      (node (ref "BAI_2,3") (pin "P$SIG0") (pinfunction "SIG0_P$SIG0") (pintype "bidirectional"))
      (node (ref "JP3") (pin "7") (pinfunction "7_7") (pintype "passive"))
      (node (ref "MXP-B") (pin "7") (pinfunction "KL_7") (pintype "passive"))
    )
    (net (code "35") (name "B_AI3") (class "Default")
      (node (ref "BAI_2,3") (pin "P$SIG1") (pinfunction "SIG1_P$SIG1") (pintype "bidirectional"))
      (node (ref "JP3") (pin "9") (pinfunction "9_9") (pintype "passive"))
      (node (ref "MXP-B") (pin "9") (pinfunction "KL_9") (pintype "passive"))
    )
    (net (code "36") (name "B_AO0") (class "Default")
      (node (ref "BAO_0,1") (pin "P$SIG0") (pinfunction "SIG0_P$SIG0") (pintype "bidirectional"))
      (node (ref "JP3") (pin "2") (pinfunction "2_2") (pintype "passive"))
      (node (ref "MXP-B") (pin "2") (pinfunction "KL_2") (pintype "passive"))
    )
    (net (code "37") (name "B_AO1") (class "Default")
      (node (ref "BAO_0,1") (pin "P$SIG1") (pinfunction "SIG1_P$SIG1") (pintype "bidirectional"))
      (node (ref "JP3") (pin "4") (pinfunction "4_4") (pintype "passive"))
      (node (ref "MXP-B") (pin "4") (pinfunction "KL_4") (pintype "passive"))
    )
    (net (code "38") (name "B_DIO0") (class "Default")
      (node (ref "JP3") (pin "11") (pinfunction "11_11") (pintype "passive"))
      (node (ref "MXP-B") (pin "11") (pinfunction "KL_11") (pintype "passive"))
    )
    (net (code "39") (name "B_DIO1") (class "Default")
      (node (ref "JP3") (pin "13") (pinfunction "13_13") (pintype "passive"))
      (node (ref "MXP-B") (pin "13") (pinfunction "KL_13") (pintype "passive"))
    )
    (net (code "40") (name "B_DIO2") (class "Default")
      (node (ref "JP3") (pin "15") (pinfunction "15_15") (pintype "passive"))
      (node (ref "MXP-B") (pin "15") (pinfunction "KL_15") (pintype "passive"))
    )
    (net (code "41") (name "B_DIO3") (class "Default")
      (node (ref "JP3") (pin "17") (pinfunction "17_17") (pintype "passive"))
      (node (ref "MXP-B") (pin "17") (pinfunction "KL_17") (pintype "passive"))
    )
    (net (code "42") (name "B_DIO4") (class "Default")
      (node (ref "JP3") (pin "19") (pinfunction "19_19") (pintype "passive"))
      (node (ref "MXP-B") (pin "19") (pinfunction "KL_19") (pintype "passive"))
    )
    (net (code "43") (name "B_DIO5") (class "Default")
      (node (ref "JP3") (pin "21") (pinfunction "21_21") (pintype "passive"))
      (node (ref "MXP-B") (pin "21") (pinfunction "KL_21") (pintype "passive"))
    )
    (net (code "44") (name "B_DIO6") (class "Default")
      (node (ref "JP3") (pin "23") (pinfunction "23_23") (pintype "passive"))
      (node (ref "MXP-B") (pin "23") (pinfunction "KL_23") (pintype "passive"))
    )
    (net (code "45") (name "B_DIO7") (class "Default")
      (node (ref "JP3") (pin "25") (pinfunction "25_25") (pintype "passive"))
      (node (ref "MXP-B") (pin "25") (pinfunction "KL_25") (pintype "passive"))
    )
    (net (code "46") (name "B_DIO8") (class "Default")
      (node (ref "JP3") (pin "27") (pinfunction "27_27") (pintype "passive"))
      (node (ref "MXP-B") (pin "27") (pinfunction "KL_27") (pintype "passive"))
    )
    (net (code "47") (name "B_DIO9") (class "Default")
      (node (ref "JP3") (pin "29") (pinfunction "29_29") (pintype "passive"))
      (node (ref "LED_MASK_1,2") (pin "P$SIG0") (pinfunction "SIG0_P$SIG0") (pintype "bidirectional"))
      (node (ref "MXP-B") (pin "29") (pinfunction "KL_29") (pintype "passive"))
      (node (ref "R13") (pin "2") (pinfunction "2_2") (pintype "passive"))
    )
    (net (code "48") (name "B_DIO10") (class "Default")
      (node (ref "JP3") (pin "31") (pinfunction "31_31") (pintype "passive"))
      (node (ref "MXP-B") (pin "31") (pinfunction "KL_31") (pintype "passive"))
    )
    (net (code "49") (name "B_DIO11") (class "Default")
      (node (ref "JP3") (pin "18") (pinfunction "18_18") (pintype "passive"))
      (node (ref "MXP-B") (pin "18") (pinfunction "KL_18") (pintype "passive"))
    )
    (net (code "50") (name "B_DIO12") (class "Default")
      (node (ref "JP3") (pin "22") (pinfunction "22_22") (pintype "passive"))
      (node (ref "LED_CUE_3") (pin "P$SIG") (pinfunction "SIG_P$SIG") (pintype "bidirectional"))
      (node (ref "MXP-B") (pin "22") (pinfunction "KL_22") (pintype "passive"))
      (node (ref "R14") (pin "2") (pinfunction "2_2") (pintype "passive"))
    )
    (net (code "51") (name "B_DIO13") (class "Default")
      (node (ref "JP3") (pin "26") (pinfunction "26_26") (pintype "passive"))
      (node (ref "MXP-B") (pin "26") (pinfunction "KL_26") (pintype "passive"))
    )
    (net (code "52") (name "B_DIO14") (class "Default")
      (node (ref "JP3") (pin "32") (pinfunction "32_32") (pintype "passive"))
      (node (ref "LED_MASK_1,2") (pin "P$SIG1") (pinfunction "SIG1_P$SIG1") (pintype "bidirectional"))
      (node (ref "MXP-B") (pin "32") (pinfunction "KL_32") (pintype "passive"))
      (node (ref "R12") (pin "2") (pinfunction "2_2") (pintype "passive"))
    )
    (net (code "53") (name "B_DIO15") (class "Default")
      (node (ref "JP3") (pin "34") (pinfunction "34_34") (pintype "passive"))
      (node (ref "MXP-B") (pin "34") (pinfunction "KL_34") (pintype "passive"))
    )
    (net (code "54") (name "B_UART.RX") (class "Default")
      (node (ref "JP3") (pin "10") (pinfunction "10_10") (pintype "passive"))
      (node (ref "MXP-B") (pin "10") (pinfunction "KL_10") (pintype "passive"))
    )
    (net (code "55") (name "B_UART.TX") (class "Default")
      (node (ref "JP3") (pin "14") (pinfunction "14_14") (pintype "passive"))
      (node (ref "MXP-B") (pin "14") (pinfunction "KL_14") (pintype "passive"))
    )
    (net (code "56") (name "DGND") (class "Default")
      (node (ref "ACTV_REC") (pin "P$GND") (pinfunction "GND_P$GND") (pintype "bidirectional"))
      (node (ref "BUCKPUCK1") (pin "LED-") (pinfunction "LED-_LED-") (pintype "bidirectional"))
      (node (ref "BUCKPUCK1") (pin "VIN-") (pinfunction "VIN-_VIN-") (pintype "bidirectional"))
      (node (ref "BUCKPUCK2") (pin "LED-") (pinfunction "LED-_LED-") (pintype "bidirectional"))
      (node (ref "BUCKPUCK2") (pin "VIN-") (pinfunction "VIN-_VIN-") (pintype "bidirectional"))
      (node (ref "BUCKPUCK3") (pin "LED-") (pinfunction "LED-_LED-") (pintype "bidirectional"))
      (node (ref "BUCKPUCK3") (pin "VIN-") (pinfunction "VIN-_VIN-") (pintype "bidirectional"))
      (node (ref "C1") (pin "-") (pinfunction "-_-") (pintype "passive"))
      (node (ref "C2") (pin "-") (pinfunction "-_-") (pintype "passive"))
      (node (ref "C3") (pin "-") (pinfunction "-_-") (pintype "passive"))
      (node (ref "C4") (pin "-") (pinfunction "-_-") (pintype "passive"))
      (node (ref "C5") (pin "-") (pinfunction "-_-") (pintype "passive"))
      (node (ref "C6") (pin "2") (pinfunction "2_2") (pintype "passive"))
      (node (ref "C7") (pin "2") (pinfunction "2_2") (pintype "passive"))
      (node (ref "CAMERA") (pin "P$GND0") (pinfunction "GND0_P$GND0") (pintype "bidirectional"))
      (node (ref "CAMERA") (pin "P$GND1") (pinfunction "GND1_P$GND1") (pintype "bidirectional"))
      (node (ref "CH1") (pin "P2") (pinfunction "2_P2") (pintype "passive"))
      (node (ref "CH2") (pin "P2") (pinfunction "2_P2") (pintype "passive"))
      (node (ref "CH3") (pin "P2") (pinfunction "2_P2") (pintype "passive"))
      (node (ref "DGND") (pin "TP") (pinfunction "TP_TP") (pintype "input"))
      (node (ref "DGND1") (pin "TP") (pinfunction "TP_TP") (pintype "input"))
      (node (ref "D_FREE1_2") (pin "P$GND0") (pinfunction "GND0_P$GND0") (pintype "bidirectional"))
      (node (ref "D_FREE1_2") (pin "P$GND1") (pinfunction "GND1_P$GND1") (pintype "bidirectional"))
      (node (ref "D_FREE3_4") (pin "P$GND0") (pinfunction "GND0_P$GND0") (pintype "bidirectional"))
      (node (ref "D_FREE3_4") (pin "P$GND1") (pinfunction "GND1_P$GND1") (pintype "bidirectional"))
      (node (ref "ISOLATED") (pin "K") (pinfunction "C_K") (pintype "passive"))
      (node (ref "JP10") (pin "GND") (pinfunction "GND_GND") (pintype "bidirectional"))
      (node (ref "JP10") (pin "GNDBREAK") (pinfunction "GNDBREAK_GNDBREAK") (pintype "bidirectional"))
      (node (ref "JP3") (pin "12") (pinfunction "12_12") (pintype "passive"))
      (node (ref "JP3") (pin "16") (pinfunction "16_16") (pintype "passive"))
      (node (ref "JP3") (pin "20") (pinfunction "20_20") (pintype "passive"))
      (node (ref "JP3") (pin "24") (pinfunction "24_24") (pintype "passive"))
      (node (ref "JP3") (pin "28") (pinfunction "28_28") (pintype "passive"))
      (node (ref "JP3") (pin "30") (pinfunction "30_30") (pintype "passive"))
      (node (ref "JP3") (pin "8") (pinfunction "8_8") (pintype "passive"))
      (node (ref "JP4") (pin "12") (pinfunction "12_12") (pintype "passive"))
      (node (ref "JP4") (pin "16") (pinfunction "16_16") (pintype "passive"))
      (node (ref "JP4") (pin "20") (pinfunction "20_20") (pintype "passive"))
      (node (ref "JP4") (pin "24") (pinfunction "24_24") (pintype "passive"))
      (node (ref "JP4") (pin "28") (pinfunction "28_28") (pintype "passive"))
      (node (ref "JP4") (pin "30") (pinfunction "30_30") (pintype "passive"))
      (node (ref "JP4") (pin "8") (pinfunction "8_8") (pintype "passive"))
      (node (ref "LED_CUE_3") (pin "P$GND") (pinfunction "GND_P$GND") (pintype "bidirectional"))
      (node (ref "LED_MASK_1,2") (pin "P$GND0") (pinfunction "GND0_P$GND0") (pintype "bidirectional"))
      (node (ref "LED_MASK_1,2") (pin "P$GND1") (pinfunction "GND1_P$GND1") (pintype "bidirectional"))
      (node (ref "LICK") (pin "P$GND0") (pinfunction "GND0_P$GND0") (pintype "bidirectional"))
      (node (ref "LICK") (pin "P$GND1") (pinfunction "GND1_P$GND1") (pintype "bidirectional"))
      (node (ref "MXP-A") (pin "12") (pinfunction "KL_12") (pintype "passive"))
      (node (ref "MXP-A") (pin "16") (pinfunction "KL_16") (pintype "passive"))
      (node (ref "MXP-A") (pin "20") (pinfunction "KL_20") (pintype "passive"))
      (node (ref "MXP-A") (pin "24") (pinfunction "KL_24") (pintype "passive"))
      (node (ref "MXP-A") (pin "28") (pinfunction "KL_28") (pintype "passive"))
      (node (ref "MXP-A") (pin "30") (pinfunction "KL_30") (pintype "passive"))
      (node (ref "MXP-A") (pin "8") (pinfunction "KL_8") (pintype "passive"))
      (node (ref "MXP-B") (pin "12") (pinfunction "KL_12") (pintype "passive"))
      (node (ref "MXP-B") (pin "16") (pinfunction "KL_16") (pintype "passive"))
      (node (ref "MXP-B") (pin "20") (pinfunction "KL_20") (pintype "passive"))
      (node (ref "MXP-B") (pin "24") (pinfunction "KL_24") (pintype "passive"))
      (node (ref "MXP-B") (pin "28") (pinfunction "KL_28") (pintype "passive"))
      (node (ref "MXP-B") (pin "30") (pinfunction "KL_30") (pintype "passive"))
      (node (ref "MXP-B") (pin "8") (pinfunction "KL_8") (pintype "passive"))
      (node (ref "OK1") (pin "4") (pinfunction "EMI_4") (pintype "passive"))
      (node (ref "OK2") (pin "4") (pinfunction "EMI_4") (pintype "passive"))
      (node (ref "POWER_LED") (pin "K") (pinfunction "C_K") (pintype "passive"))
      (node (ref "Q2") (pin "E") (pinfunction "E_E") (pintype "passive"))
      (node (ref "Q4") (pin "E") (pinfunction "E_E") (pintype "passive"))
      (node (ref "Q6") (pin "E") (pinfunction "E_E") (pintype "passive"))
      (node (ref "R3") (pin "1") (pinfunction "1_1") (pintype "passive"))
      (node (ref "R4") (pin "1") (pinfunction "1_1") (pintype "passive"))
      (node (ref "SHUTTER") (pin "P$GND0") (pinfunction "GND0_P$GND0") (pintype "bidirectional"))
      (node (ref "SHUTTER") (pin "P$GND1") (pinfunction "GND1_P$GND1") (pintype "bidirectional"))
      (node (ref "SLN") (pin "P$GND0") (pinfunction "GND0_P$GND0") (pintype "bidirectional"))
      (node (ref "SLN") (pin "P$GND1") (pinfunction "GND1_P$GND1") (pintype "bidirectional"))
      (node (ref "T1") (pin "3") (pinfunction "S_3") (pintype "passive"))
      (node (ref "T2") (pin "3") (pinfunction "S_3") (pintype "passive"))
      (node (ref "U1") (pin "4") (pinfunction "GND_4") (pintype "passive"))
    )
    (net (code "57") (name "GND-ISO") (class "Default")
      (node (ref "BAT1") (pin "-") (pinfunction "-_-") (pintype "power_in"))
      (node (ref "C10") (pin "2") (pinfunction "2_2") (pintype "passive"))
      (node (ref "C11") (pin "2") (pinfunction "2_2") (pintype "passive"))
      (node (ref "C8") (pin "2") (pinfunction "2_2") (pintype "passive"))
      (node (ref "C9") (pin "2") (pinfunction "2_2") (pintype "passive"))
      (node (ref "GND-ISO") (pin "TP") (pinfunction "TP_TP") (pintype "input"))
      (node (ref "LICK_INPUTS") (pin "P$GND0") (pinfunction "GND0_P$GND0") (pintype "bidirectional"))
      (node (ref "LICK_INPUTS") (pin "P$GND1") (pinfunction "GND1_P$GND1") (pintype "bidirectional"))
      (node (ref "OK1") (pin "2") (pinfunction "C_2") (pintype "passive"))
      (node (ref "OK2") (pin "2") (pinfunction "C_2") (pintype "passive"))
      (node (ref "R17") (pin "2") (pinfunction "2_2") (pintype "passive"))
      (node (ref "R18") (pin "2") (pinfunction "2_2") (pintype "passive"))
      (node (ref "S2") (pin "5") (pinfunction "P2_5") (pintype "passive"))
      (node (ref "TSH_L") (pin "A") (pinfunction "A_A") (pintype "passive"))
      (node (ref "TSH_R") (pin "A") (pinfunction "A_A") (pintype "passive"))
      (node (ref "U$1") (pin "P1") (pinfunction "P$1_P1") (pintype "bidirectional"))
      (node (ref "U2") (pin "1") (pinfunction "GND_1") (pintype "passive"))
      (node (ref "U2") (pin "2") (pinfunction "V-_2") (pintype "power_in"))
      (node (ref "U3") (pin "1") (pinfunction "GND_1") (pintype "passive"))
      (node (ref "U3") (pin "2") (pinfunction "V-_2") (pintype "power_in"))
    )
    (net (code "58") (name "LICK_L_IN") (class "Default")
      (node (ref "D4") (pin "A") (pinfunction "A_A") (pintype "passive"))
      (node (ref "R15") (pin "1") (pinfunction "1_1") (pintype "passive"))
      (node (ref "U$1") (pin "P2") (pinfunction "P$2_P2") (pintype "bidirectional"))
      (node (ref "U2") (pin "4") (pinfunction "IN-_4") (pintype "input"))
    )
    (net (code "59") (name "LICK_R_IN") (class "Default")
      (node (ref "D5") (pin "A") (pinfunction "A_A") (pintype "passive"))
      (node (ref "R16") (pin "1") (pinfunction "1_1") (pintype "passive"))
      (node (ref "U$1") (pin "P3") (pinfunction "P$3_P3") (pintype "bidirectional"))
      (node (ref "U3") (pin "4") (pinfunction "IN-_4") (pintype "input"))
    )
    (net (code "60") (name "N$6") (class "Default")
      (node (ref "R2") (pin "2") (pinfunction "2_2") (pintype "passive"))
      (node (ref "R4") (pin "2") (pinfunction "2_2") (pintype "passive"))
      (node (ref "T1") (pin "1") (pinfunction "G_1") (pintype "passive"))
    )
    (net (code "61") (name "N$16") (class "Default")
      (node (ref "BUCKPUCK1") (pin "VIN+") (pinfunction "VIN+_VIN+") (pintype "bidirectional"))
      (node (ref "BUCKPUCK2") (pin "VIN+") (pinfunction "VIN+_VIN+") (pintype "bidirectional"))
      (node (ref "BUCKPUCK3") (pin "VIN+") (pinfunction "VIN+_VIN+") (pintype "bidirectional"))
      (node (ref "C1") (pin "+") (pinfunction "+_+") (pintype "passive"))
      (node (ref "C2") (pin "+") (pinfunction "+_+") (pintype "passive"))
      (node (ref "C3") (pin "+") (pinfunction "+_+") (pintype "passive"))
      (node (ref "C4") (pin "+") (pinfunction "+_+") (pintype "passive"))
      (node (ref "D1") (pin "C") (pinfunction "C_C") (pintype "passive"))
      (node (ref "U1") (pin "1") (pinfunction "VI_1") (pintype "input"))
      (node (ref "VIN") (pin "TP") (pinfunction "TP_TP") (pintype "input"))
    )
    (net (code "62") (name "Net-(AUDIO-GND0)") (class "Default")
      (node (ref "AUDIO") (pin "P$GND0") (pinfunction "GND0_P$GND0") (pintype "bidirectional"))
      (node (ref "AUDIO") (pin "P$GND1") (pinfunction "GND1_P$GND1") (pintype "bidirectional"))
      (node (ref "JP1") (pin "SLEEVE") (pinfunction "SLEEVE_SLEEVE") (pintype "bidirectional"))
      (node (ref "JP2") (pin "SLEEVE") (pinfunction "SLEEVE_SLEEVE") (pintype "bidirectional"))
    )
    (net (code "63") (name "Net-(AUDIO-SIG0)") (class "Default")
      (node (ref "AUDIO") (pin "P$SIG0") (pinfunction "SIG0_P$SIG0") (pintype "bidirectional"))
      (node (ref "JP1") (pin "RING") (pinfunction "RIGHT_RING") (pintype "bidirectional"))
      (node (ref "JP2") (pin "RING") (pinfunction "RIGHT_RING") (pintype "bidirectional"))
    )
    (net (code "64") (name "Net-(AUDIO-SIG1)") (class "Default")
      (node (ref "AUDIO") (pin "P$SIG1") (pinfunction "SIG1_P$SIG1") (pintype "bidirectional"))
      (node (ref "JP1") (pin "TIP") (pinfunction "LEFT_TIP") (pintype "bidirectional"))
      (node (ref "JP2") (pin "TIP") (pinfunction "LEFT_TIP") (pintype "bidirectional"))
    )
    (net (code "65") (name "Net-(BUCKPUCK1-PadCTRL)") (class "Default")
      (node (ref "BUCKPUCK1") (pin "CTRL") (pinfunction "CTRL_CTRL") (pintype "bidirectional"))
      (node (ref "Q1") (pin "C") (pinfunction "C_C") (pintype "passive"))
    )
    (net (code "66") (name "Net-(BUCKPUCK1-PadREF)") (class "Default")
      (node (ref "BUCKPUCK1") (pin "REF") (pinfunction "REF_REF") (pintype "bidirectional"))
      (node (ref "Q1") (pin "E") (pinfunction "E_E") (pintype "passive"))
      (node (ref "R6") (pin "1") (pinfunction "1_1") (pintype "passive"))
    )
    (net (code "67") (name "Net-(BUCKPUCK2-PadCTRL)") (class "Default")
      (node (ref "BUCKPUCK2") (pin "CTRL") (pinfunction "CTRL_CTRL") (pintype "bidirectional"))
      (node (ref "Q3") (pin "C") (pinfunction "C_C") (pintype "passive"))
    )
    (net (code "68") (name "Net-(BUCKPUCK2-PadREF)") (class "Default")
      (node (ref "BUCKPUCK2") (pin "REF") (pinfunction "REF_REF") (pintype "bidirectional"))
      (node (ref "Q3") (pin "E") (pinfunction "E_E") (pintype "passive"))
      (node (ref "R7") (pin "1") (pinfunction "1_1") (pintype "passive"))
    )
    (net (code "69") (name "Net-(BUCKPUCK3-PadCTRL)") (class "Default")
      (node (ref "BUCKPUCK3") (pin "CTRL") (pinfunction "CTRL_CTRL") (pintype "bidirectional"))
      (node (ref "Q5") (pin "C") (pinfunction "C_C") (pintype "passive"))
    )
    (net (code "70") (name "Net-(BUCKPUCK3-PadREF)") (class "Default")
      (node (ref "BUCKPUCK3") (pin "REF") (pinfunction "REF_REF") (pintype "bidirectional"))
      (node (ref "Q5") (pin "E") (pinfunction "E_E") (pintype "passive"))
      (node (ref "R8") (pin "1") (pinfunction "1_1") (pintype "passive"))
    )
    (net (code "71") (name "Net-(C10-Pad1)") (class "Default")
      (node (ref "C10") (pin "1") (pinfunction "1_1") (pintype "passive"))
      (node (ref "R24") (pin "2") (pinfunction "2_2") (pintype "passive"))
    )
    (net (code "72") (name "Net-(C11-Pad1)") (class "Default")
      (node (ref "C11") (pin "1") (pinfunction "1_1") (pintype "passive"))
      (node (ref "R25") (pin "2") (pinfunction "2_2") (pintype "passive"))
    )
    (net (code "73") (name "Net-(CH1-1)") (class "Default")
      (node (ref "BUCKPUCK1") (pin "LED+") (pinfunction "LED+_LED+") (pintype "bidirectional"))
      (node (ref "CH1") (pin "P1") (pinfunction "1_P1") (pintype "passive"))
    )
    (net (code "74") (name "Net-(CH2-1)") (class "Default")
      (node (ref "BUCKPUCK2") (pin "LED+") (pinfunction "LED+_LED+") (pintype "bidirectional"))
      (node (ref "CH2") (pin "P1") (pinfunction "1_P1") (pintype "passive"))
    )
    (net (code "75") (name "Net-(CH3-1)") (class "Default")
      (node (ref "BUCKPUCK3") (pin "LED+") (pinfunction "LED+_LED+") (pintype "bidirectional"))
      (node (ref "CH3") (pin "P1") (pinfunction "1_P1") (pintype "passive"))
    )
    (net (code "76") (name "Net-(D2-C)") (class "Default")
      (node (ref "D2") (pin "A") (pinfunction "C_A") (pintype "passive"))
      (node (ref "J1") (pin "2") (pinfunction "2_2") (pintype "passive"))
      (node (ref "T1") (pin "2") (pinfunction "D_2") (pintype "passive"))
      (node (ref "T1") (pin "4") (pinfunction "D_4") (pintype "passive"))
    )
    (net (code "77") (name "Net-(D3-C)") (class "Default")
      (node (ref "D3") (pin "A") (pinfunction "C_A") (pintype "passive"))
      (node (ref "J2") (pin "2") (pinfunction "2_2") (pintype "passive"))
      (node (ref "T2") (pin "2") (pinfunction "D_2") (pintype "passive"))
      (node (ref "T2") (pin "4") (pinfunction "D_4") (pintype "passive"))
    )
    (net (code "78") (name "Net-(ISOLATED-PadA)") (class "Default")
      (node (ref "ISOLATED") (pin "A") (pinfunction "A_A") (pintype "passive"))
      (node (ref "R23") (pin "1") (pinfunction "1_1") (pintype "passive"))
    )
    (net (code "79") (name "Net-(JP5-P$2)") (class "Default")
      (node (ref "J2") (pin "1") (pinfunction "1_1") (pintype "passive"))
      (node (ref "JP5") (pin "2") (pinfunction "P$2_2") (pintype "bidirectional"))
    )
    (net (code "80") (name "Net-(JP6-P$2)") (class "Default")
      (node (ref "J1") (pin "1") (pinfunction "1_1") (pintype "passive"))
      (node (ref "JP6") (pin "2") (pinfunction "P$2_2") (pintype "bidirectional"))
    )
    (net (code "81") (name "Net-(JP10-PadPWR)") (class "Default")
      (node (ref "JP10") (pin "PWR") (pinfunction "PWR_PWR") (pintype "bidirectional"))
      (node (ref "S1") (pin "2") (pinfunction "2_2") (pintype "passive"))
    )
    (net (code "82") (name "Net-(LICK_INPUTS-SIG0)") (class "Default")
      (node (ref "D4") (pin "C") (pinfunction "C_C") (pintype "passive"))
      (node (ref "LICK_INPUTS") (pin "P$SIG0") (pinfunction "SIG0_P$SIG0") (pintype "bidirectional"))
    )
    (net (code "83") (name "Net-(LICK_INPUTS-SIG1)") (class "Default")
      (node (ref "D5") (pin "C") (pinfunction "C_C") (pintype "passive"))
      (node (ref "LICK_INPUTS") (pin "P$SIG1") (pinfunction "SIG1_P$SIG1") (pintype "bidirectional"))
    )
    (net (code "84") (name "Net-(OK1-A)") (class "Default")
      (node (ref "OK1") (pin "1") (pinfunction "A_1") (pintype "passive"))
      (node (ref "R19") (pin "1") (pinfunction "1_1") (pintype "passive"))
    )
    (net (code "85") (name "Net-(OK1-COL)") (class "Default")
      (node (ref "DNP1") (pin "2") (pinfunction "2_2") (pintype "passive"))
      (node (ref "OK1") (pin "5") (pinfunction "COL_5") (pintype "passive"))
      (node (ref "R21") (pin "1") (pinfunction "1_1") (pintype "passive"))
    )
    (net (code "86") (name "Net-(OK2-A)") (class "Default")
      (node (ref "OK2") (pin "1") (pinfunction "A_1") (pintype "passive"))
      (node (ref "R20") (pin "1") (pinfunction "1_1") (pintype "passive"))
    )
    (net (code "87") (name "Net-(OK2-COL)") (class "Default")
      (node (ref "DNP2") (pin "2") (pinfunction "2_2") (pintype "passive"))
      (node (ref "OK2") (pin "5") (pinfunction "COL_5") (pintype "passive"))
      (node (ref "R22") (pin "1") (pinfunction "1_1") (pintype "passive"))
    )
    (net (code "88") (name "Net-(POWER_LED-PadA)") (class "Default")
      (node (ref "POWER_LED") (pin "A") (pinfunction "A_A") (pintype "passive"))
      (node (ref "R5") (pin "1") (pinfunction "1_1") (pintype "passive"))
    )
    (net (code "89") (name "Net-(Q1-PadB)") (class "Default")
      (node (ref "Q1") (pin "B") (pinfunction "B_B") (pintype "passive"))
      (node (ref "R6") (pin "2") (pinfunction "2_2") (pintype "passive"))
      (node (ref "R9") (pin "1") (pinfunction "1_1") (pintype "passive"))
    )
    (net (code "90") (name "Net-(Q2-PadB)") (class "Default")
      (node (ref "Q2") (pin "B") (pinfunction "B_B") (pintype "passive"))
      (node (ref "R12") (pin "1") (pinfunction "1_1") (pintype "passive"))
    )
    (net (code "91") (name "Net-(Q2-PadC)") (class "Default")
      (node (ref "Q2") (pin "C") (pinfunction "C_C") (pintype "passive"))
      (node (ref "R9") (pin "2") (pinfunction "2_2") (pintype "passive"))
    )
    (net (code "92") (name "Net-(Q3-PadB)") (class "Default")
      (node (ref "Q3") (pin "B") (pinfunction "B_B") (pintype "passive"))
      (node (ref "R10") (pin "1") (pinfunction "1_1") (pintype "passive"))
      (node (ref "R7") (pin "2") (pinfunction "2_2") (pintype "passive"))
    )
    (net (code "93") (name "Net-(Q4-PadB)") (class "Default")
      (node (ref "Q4") (pin "B") (pinfunction "B_B") (pintype "passive"))
      (node (ref "R13") (pin "1") (pinfunction "1_1") (pintype "passive"))
    )
    (net (code "94") (name "Net-(Q4-PadC)") (class "Default")
      (node (ref "Q4") (pin "C") (pinfunction "C_C") (pintype "passive"))
      (node (ref "R10") (pin "2") (pinfunction "2_2") (pintype "passive"))
    )
    (net (code "95") (name "Net-(Q5-PadB)") (class "Default")
      (node (ref "Q5") (pin "B") (pinfunction "B_B") (pintype "passive"))
      (node (ref "R11") (pin "1") (pinfunction "1_1") (pintype "passive"))
      (node (ref "R8") (pin "2") (pinfunction "2_2") (pintype "passive"))
    )
    (net (code "96") (name "Net-(Q6-PadB)") (class "Default")
      (node (ref "Q6") (pin "B") (pinfunction "B_B") (pintype "passive"))
      (node (ref "R14") (pin "1") (pinfunction "1_1") (pintype "passive"))
    )
    (net (code "97") (name "Net-(Q6-PadC)") (class "Default")
      (node (ref "Q6") (pin "C") (pinfunction "C_C") (pintype "passive"))
      (node (ref "R11") (pin "2") (pinfunction "2_2") (pintype "passive"))
    )
    (net (code "98") (name "Net-(S2-P3)") (class "Default")
      (node (ref "BAT1") (pin "+") (pinfunction "+_+") (pintype "power_in"))
      (node (ref "S2") (pin "8") (pinfunction "P3_8") (pintype "passive"))
    )
    (net (code "99") (name "Net-(S2-S1)") (class "Default")
      (node (ref "R23") (pin "2") (pinfunction "2_2") (pintype "passive"))
      (node (ref "S2") (pin "3") (pinfunction "S1_3") (pintype "passive"))
    )
    (net (code "100") (name "Net-(T2-G)") (class "Default")
      (node (ref "R1") (pin "2") (pinfunction "2_2") (pintype "passive"))
      (node (ref "R3") (pin "2") (pinfunction "2_2") (pintype "passive"))
      (node (ref "T2") (pin "1") (pinfunction "G_1") (pintype "passive"))
    )
    (net (code "101") (name "Net-(U2-HYST)") (class "Default")
      (node (ref "HYST_L") (pin "E") (pinfunction "E_E") (pintype "passive"))
      (node (ref "R17") (pin "1") (pinfunction "1_1") (pintype "passive"))
      (node (ref "RH_L") (pin "2") (pinfunction "2_2") (pintype "passive"))
      (node (ref "U2") (pin "5") (pinfunction "HYST_5") (pintype "input"))
    )
    (net (code "102") (name "Net-(U2-IN+)") (class "Default")
      (node (ref "TSH_L") (pin "S") (pinfunction "S_S") (pintype "passive"))
      (node (ref "U2") (pin "3") (pinfunction "IN+_3") (pintype "input"))
    )
    (net (code "103") (name "Net-(U2-OUT)") (class "Default")
      (node (ref "R19") (pin "2") (pinfunction "2_2") (pintype "passive"))
      (node (ref "U2") (pin "8") (pinfunction "OUT_8") (pintype "output"))
    )
    (net (code "104") (name "Net-(U2-REF)") (class "Default")
      (node (ref "HYST_L") (pin "A") (pinfunction "A_A") (pintype "passive"))
      (node (ref "HYST_L") (pin "S") (pinfunction "S_S") (pintype "passive"))
      (node (ref "R24") (pin "1") (pinfunction "1_1") (pintype "passive"))
      (node (ref "RH_L") (pin "1") (pinfunction "1_1") (pintype "passive"))
      (node (ref "U2") (pin "6") (pinfunction "REF_6") (pintype "output"))
    )
    (net (code "105") (name "Net-(U3-HYST)") (class "Default")
      (node (ref "HYST_R") (pin "E") (pinfunction "E_E") (pintype "passive"))
      (node (ref "R18") (pin "1") (pinfunction "1_1") (pintype "passive"))
      (node (ref "RH_R") (pin "2") (pinfunction "2_2") (pintype "passive"))
      (node (ref "U3") (pin "5") (pinfunction "HYST_5") (pintype "input"))
    )
    (net (code "106") (name "Net-(U3-IN+)") (class "Default")
      (node (ref "TSH_R") (pin "S") (pinfunction "S_S") (pintype "passive"))
      (node (ref "U3") (pin "3") (pinfunction "IN+_3") (pintype "input"))
    )
    (net (code "107") (name "Net-(U3-OUT)") (class "Default")
      (node (ref "R20") (pin "2") (pinfunction "2_2") (pintype "passive"))
      (node (ref "U3") (pin "8") (pinfunction "OUT_8") (pintype "output"))
    )
    (net (code "108") (name "Net-(U3-REF)") (class "Default")
      (node (ref "HYST_R") (pin "A") (pinfunction "A_A") (pintype "passive"))
      (node (ref "HYST_R") (pin "S") (pinfunction "S_S") (pintype "passive"))
      (node (ref "R25") (pin "1") (pinfunction "1_1") (pintype "passive"))
      (node (ref "RH_R") (pin "1") (pinfunction "1_1") (pintype "passive"))
      (node (ref "U3") (pin "6") (pinfunction "REF_6") (pintype "output"))
    )
    (net (code "109") (name "VCC") (class "Default")
      (node (ref "C5") (pin "+") (pinfunction "+_+") (pintype "passive"))
      (node (ref "D2") (pin "C") (pinfunction "A_C") (pintype "passive"))
      (node (ref "D3") (pin "C") (pinfunction "A_C") (pintype "passive"))
      (node (ref "JP5") (pin "1") (pinfunction "P$1_1") (pintype "bidirectional"))
      (node (ref "JP6") (pin "1") (pinfunction "P$1_1") (pintype "bidirectional"))
      (node (ref "R5") (pin "2") (pinfunction "2_2") (pintype "passive"))
      (node (ref "U1") (pin "3") (pinfunction "VO_3") (pintype "passive"))
      (node (ref "VSOLN") (pin "TP") (pinfunction "TP_TP") (pintype "input"))
    )
    (net (code "110") (name "VIN") (class "Default")
      (node (ref "D1") (pin "A") (pinfunction "A_A") (pintype "passive"))
      (node (ref "S1") (pin "1") (pinfunction "1_1") (pintype "passive"))
    )
    (net (code "111") (name "unconnected-(OK1-BAS-Pad6)") (class "Default")
      (node (ref "OK1") (pin "6") (pinfunction "BAS_6") (pintype "passive"))
    )
    (net (code "112") (name "unconnected-(OK2-BAS-Pad6)") (class "Default")
      (node (ref "OK2") (pin "6") (pinfunction "BAS_6") (pintype "passive"))
    )
    (net (code "113") (name "unconnected-(S1-Pad3)") (class "Default")
      (node (ref "S1") (pin "3") (pinfunction "3_3") (pintype "passive"))
    )
    (net (code "114") (name "unconnected-(S2-O3-Pad7)") (class "Default")
      (node (ref "S2") (pin "7") (pinfunction "O3_7") (pintype "passive"))
    )
    (net (code "115") (name "unconnected-(S2-S2-Pad6)") (class "Default")
      (node (ref "S2") (pin "6") (pinfunction "S2_6") (pintype "passive"))
    )
  )
)
